# 36V_HV_Supply.net
KiCad netlist of a schematic drawn in Altium Designer
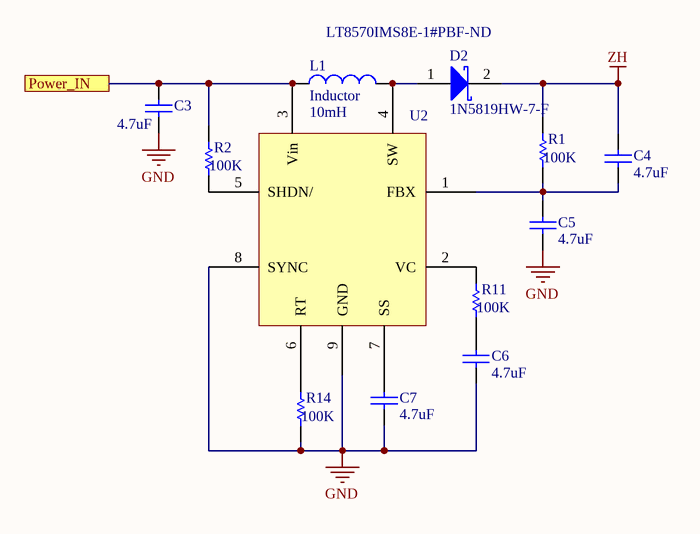
[diagram p0: 36V_HV_Supply.SchDoc]

(export (version "E")
  (design (tool "Eeschema 10.0.6"))
  (components
    (comp (ref "C3")
      (value "4.7uF")
      (footprint "CAPC1210(3225)100_M")
      (description "CAP CER 4.7UF 50V X7R 1210")
      (fields
        (field (name "MANUFACTURER") "Murata")
        (field (name "MANUFACTURER PART NUMBER") "GCM32ER71H475KA55K")
      )
      (libsource (lib "Altium Content Vault") (part "CAP"))
    )
    (comp (ref "C4")
      (value "4.7uF")
      (footprint "CAPC1210(3225)100_M")
      (description "CAP CER 4.7UF 50V X7R 1210")
      (fields
        (field (name "MANUFACTURER") "Murata")
        (field (name "MANUFACTURER PART NUMBER") "GCM32ER71H475KA55K")
      )
      (libsource (lib "Altium Content Vault") (part "CAP"))
    )
    (comp (ref "C5")
      (value "4.7uF")
      (footprint "CAPC1210(3225)100_M")
      (description "CAP CER 4.7UF 50V X7R 1210")
      (fields
        (field (name "MANUFACTURER") "Murata")
        (field (name "MANUFACTURER PART NUMBER") "GCM32ER71H475KA55K")
      )
      (libsource (lib "Altium Content Vault") (part "CAP"))
    )
    (comp (ref "C6")
      (value "4.7uF")
      (footprint "CAPC1210(3225)100_M")
      (description "CAP CER 4.7UF 50V X7R 1210")
      (fields
        (field (name "MANUFACTURER") "Murata")
        (field (name "MANUFACTURER PART NUMBER") "GCM32ER71H475KA55K")
      )
      (libsource (lib "Altium Content Vault") (part "CAP"))
    )
    (comp (ref "C7")
      (value "4.7uF")
      (footprint "CAPC1210(3225)100_M")
      (description "CAP CER 4.7UF 50V X7R 1210")
      (fields
        (field (name "MANUFACTURER") "Murata")
        (field (name "MANUFACTURER PART NUMBER") "GCM32ER71H475KA55K")
      )
      (libsource (lib "Altium Content Vault") (part "CAP"))
    )
    (comp (ref "D2")
      (value "1N5819HW-7-F")
      (footprint "DIOD-SOD-123-2_V")
      (fields (field (name "MANUFACTURER") "Diodes Inc"))
      (libsource (lib "Altium Content Vault") (part "DIOD-DSKY-A1K2-2"))
    )
    (comp (ref "L1")
      (value "Inductor")
      (footprint "0402-A")
      (fields (field (name "ALTIUM_VALUE") "10mH") (field (name "PUBLISHER") "Altium Limited"))
      (libsource (lib "Miscellaneous Devices") (part "Inductor"))
    )
    (comp (ref "R1")
      (value "RES SMD 100K OHM 1% 1/8W 0805")
      (footprint "RESC0805(2012)_M")
      (fields
        (field (name "MANUFACTURER") "Vishay")
        (field (name "MANUFACTURER PART NUMBER") "CRCW0805100KFKEA")
        (field (name "TOLERANCE") "1%")
        (field (name "RESISTANCE") "100K")
      )
      (libsource (lib "Altium Content Vault") (part "CMP-1013-00017-1"))
    )
    (comp (ref "R2")
      (value "RES SMD 100K OHM 1% 1/8W 0805")
      (footprint "RESC0805(2012)_M")
      (fields
        (field (name "MANUFACTURER") "Vishay")
        (field (name "MANUFACTURER PART NUMBER") "CRCW0805100KFKEA")
        (field (name "TOLERANCE") "1%")
        (field (name "RESISTANCE") "100K")
      )
      (libsource (lib "Altium Content Vault") (part "CMP-1013-00017-1"))
    )
    (comp (ref "R11")
      (value "RES SMD 100K OHM 1% 1/8W 0805")
      (footprint "RESC0805(2012)_M")
      (fields
        (field (name "MANUFACTURER") "Vishay")
        (field (name "MANUFACTURER PART NUMBER") "CRCW0805100KFKEA")
        (field (name "TOLERANCE") "1%")
        (field (name "RESISTANCE") "100K")
      )
      (libsource (lib "Altium Content Vault") (part "CMP-1013-00017-1"))
    )
    (comp (ref "R14")
      (value "RES SMD 100K OHM 1% 1/8W 0805")
      (footprint "RESC0805(2012)_M")
      (fields
        (field (name "MANUFACTURER") "Vishay")
        (field (name "MANUFACTURER PART NUMBER") "CRCW0805100KFKEA")
        (field (name "TOLERANCE") "1%")
        (field (name "RESISTANCE") "100K")
      )
      (libsource (lib "Altium Content Vault") (part "CMP-1013-00017-1"))
    )
    (comp (ref "U2")
      (value "LT8570")
      (footprint "LT8570-MSOP")
      (fields (field (name "SUPPLIER PART NUMBER 1") "LT8570IMS8E-1#PBF-ND"))
      (libsource (lib "ZLS_Schematic_lib") (part "LT8570"))
    )
  )
  (nets
    (net (code "1") (name "/Power_IN") (class "Default")
      (node (ref "C3") (pin "2") (pinfunction "2_2") (pintype "passive"))
      (node (ref "L1") (pin "1") (pinfunction "1_1") (pintype "passive"))
      (node (ref "R2") (pin "1") (pinfunction "1_1") (pintype "passive"))
      (node (ref "U2") (pin "3") (pinfunction "Vin_3") (pintype "passive"))
    )
    (net (code "2") (name "GND") (class "Default")
      (node (ref "C3") (pin "1") (pinfunction "1_1") (pintype "passive"))
      (node (ref "C5") (pin "1") (pinfunction "1_1") (pintype "passive"))
      (node (ref "C6") (pin "1") (pinfunction "1_1") (pintype "passive"))
      (node (ref "C7") (pin "1") (pinfunction "1_1") (pintype "passive"))
      (node (ref "R14") (pin "2") (pinfunction "2_2") (pintype "passive"))
      (node (ref "U2") (pin "8") (pinfunction "SYNC_8") (pintype "passive"))
      (node (ref "U2") (pin "9") (pinfunction "GND_9") (pintype "passive"))
    )
    (net (code "3") (name "Net-(C6-Pad2)") (class "Default")
      (node (ref "C6") (pin "2") (pinfunction "2_2") (pintype "passive"))
      (node (ref "R11") (pin "2") (pinfunction "2_2") (pintype "passive"))
    )
    (net (code "4") (name "Net-(D2-A)") (class "Default")
      (node (ref "D2") (pin "1") (pinfunction "A_1") (pintype "passive"))
      (node (ref "L1") (pin "2") (pinfunction "2_2") (pintype "passive"))
      (node (ref "U2") (pin "4") (pinfunction "SW_4") (pintype "passive"))
    )
    (net (code "5") (name "Net-(U2-FBX)") (class "Default")
      (node (ref "C4") (pin "1") (pinfunction "1_1") (pintype "passive"))
      (node (ref "C5") (pin "2") (pinfunction "2_2") (pintype "passive"))
      (node (ref "R1") (pin "2") (pinfunction "2_2") (pintype "passive"))
      (node (ref "U2") (pin "1") (pinfunction "FBX_1") (pintype "passive"))
    )
    (net (code "6") (name "Net-(U2-RT)") (class "Default")
      (node (ref "R14") (pin "1") (pinfunction "1_1") (pintype "passive"))
      (node (ref "U2") (pin "6") (pinfunction "RT_6") (pintype "passive"))
    )
    (net (code "7") (name "Net-(U2-SHDN{slash})") (class "Default")
      (node (ref "R2") (pin "2") (pinfunction "2_2") (pintype "passive"))
      (node (ref "U2") (pin "5") (pinfunction "SHDN/_5") (pintype "passive"))
    )
    (net (code "8") (name "Net-(U2-SS)") (class "Default")
      (node (ref "C7") (pin "2") (pinfunction "2_2") (pintype "passive"))
      (node (ref "U2") (pin "7") (pinfunction "SS_7") (pintype "passive"))
    )
    (net (code "9") (name "Net-(U2-VC)") (class "Default")
      (node (ref "R11") (pin "1") (pinfunction "1_1") (pintype "passive"))
      (node (ref "U2") (pin "2") (pinfunction "VC_2") (pintype "passive"))
    )
    (net (code "10") (name "ZH") (class "Default")
      (node (ref "C4") (pin "2") (pinfunction "2_2") (pintype "passive"))
      (node (ref "D2") (pin "2") (pinfunction "K_2") (pintype "passive"))
      (node (ref "R1") (pin "1") (pinfunction "1_1") (pintype "passive"))
    )
  )
)
